# PCB-MIDDLE_FINAL.net
KiCad netlist of a schematic drawn in EAGLE
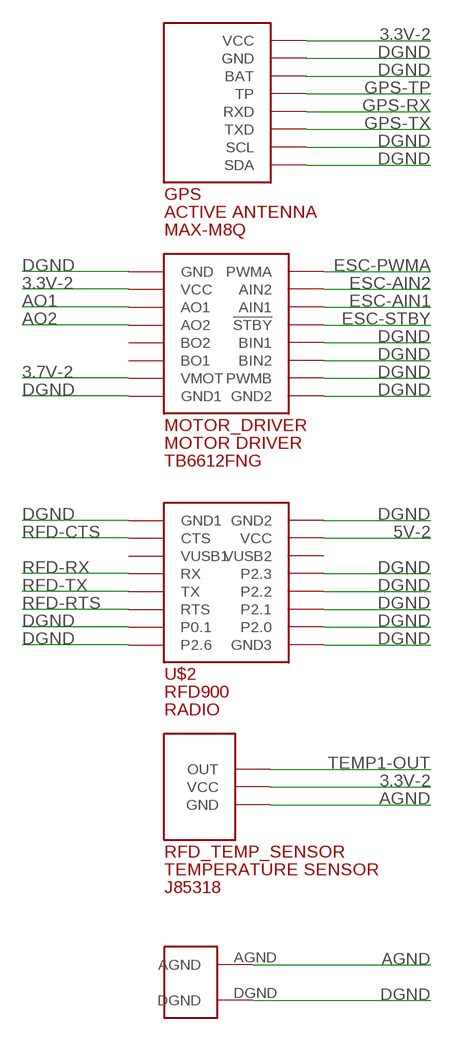
[diagram p0: schematic, sheet 1, part 1 of 2]
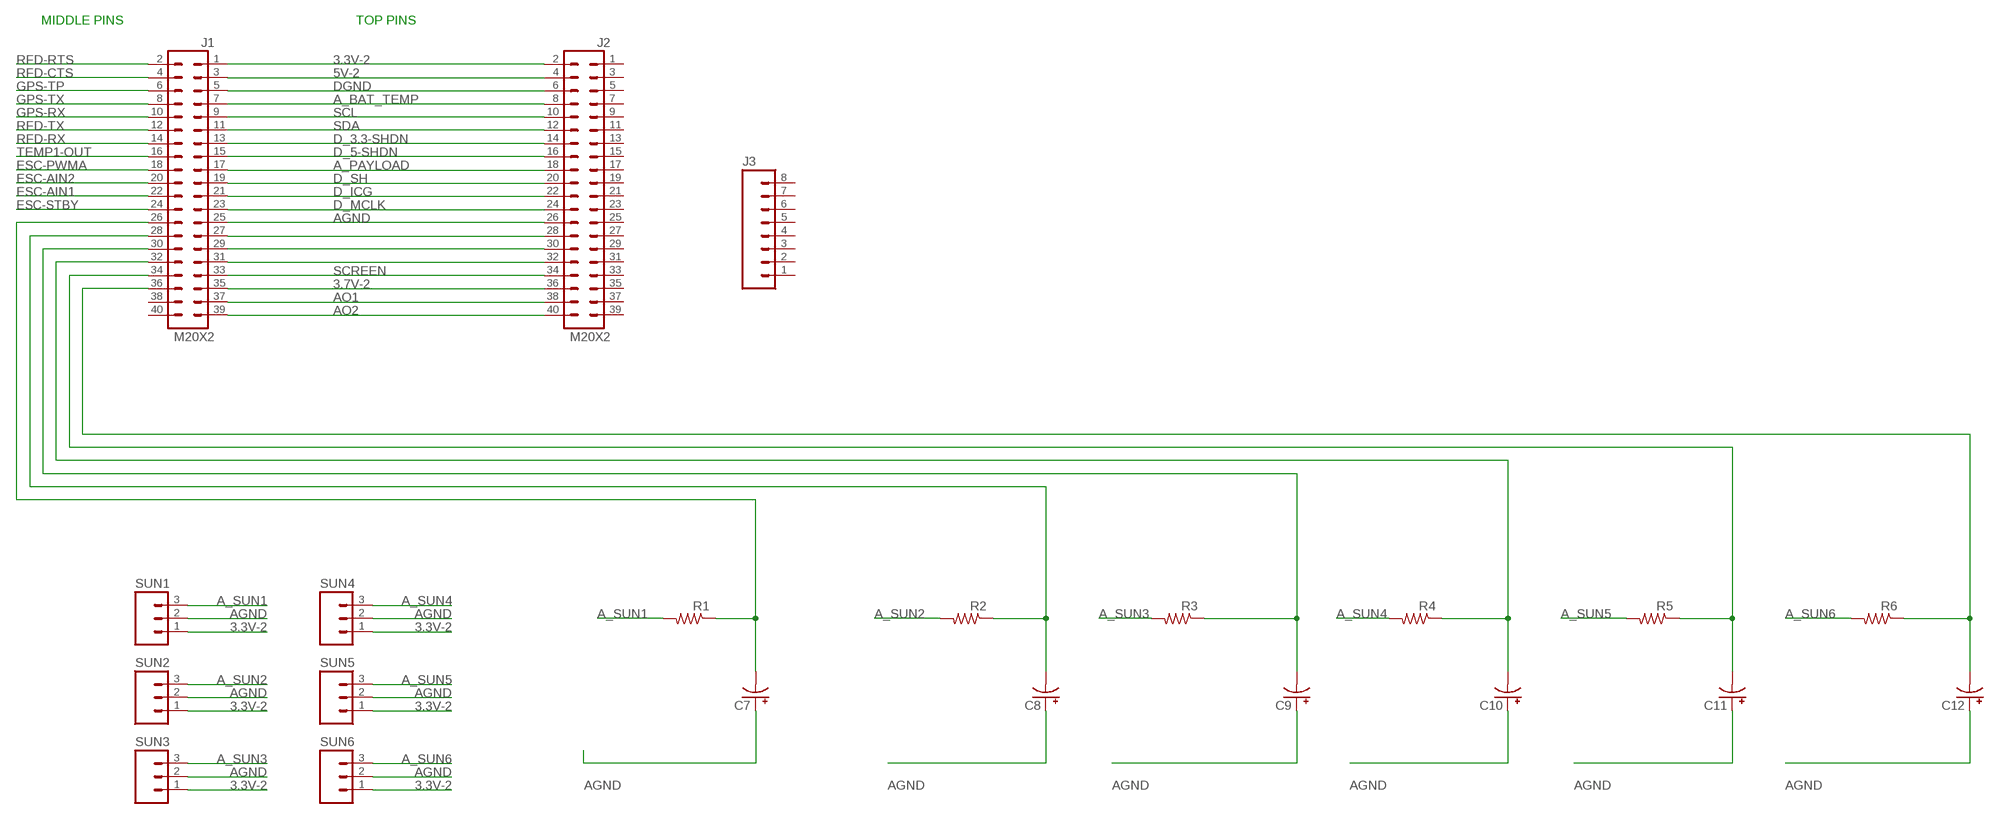
[diagram p1: schematic, sheet 1, part 2 of 2]

(export (version "E")
  (design (tool "Eeschema 10.0.6"))
  (components
    (comp (ref "C7")
      (value "100UF-25V-20%(PTH)")
      (footprint "eagle-import:CPOL-RADIAL-100UF-25V")
      (libsource (lib "eagle-import") (part "100UF-25V-20%(PTH)"))
    )
    (comp (ref "C8")
      (value "100UF-25V-20%(PTH)")
      (footprint "eagle-import:CPOL-RADIAL-100UF-25V")
      (libsource (lib "eagle-import") (part "100UF-25V-20%(PTH)"))
    )
    (comp (ref "C9")
      (value "100UF-25V-20%(PTH)")
      (footprint "eagle-import:CPOL-RADIAL-100UF-25V")
      (libsource (lib "eagle-import") (part "100UF-25V-20%(PTH)"))
    )
    (comp (ref "C10")
      (value "100UF-25V-20%(PTH)")
      (footprint "eagle-import:CPOL-RADIAL-100UF-25V")
      (libsource (lib "eagle-import") (part "100UF-25V-20%(PTH)"))
    )
    (comp (ref "C11")
      (value "100UF-25V-20%(PTH)")
      (footprint "eagle-import:CPOL-RADIAL-100UF-25V")
      (libsource (lib "eagle-import") (part "100UF-25V-20%(PTH)"))
    )
    (comp (ref "C12")
      (value "100UF-25V-20%(PTH)")
      (footprint "eagle-import:CPOL-RADIAL-100UF-25V")
      (libsource (lib "eagle-import") (part "100UF-25V-20%(PTH)"))
    )
    (comp (ref "GPS")
      (value "MAX-M8QDIP8")
      (footprint "eagle-import:DIP8")
      (libsource (lib "eagle-import") (part "MAX-M8QDIP8"))
    )
    (comp (ref "J1")
      (value "M20X2")
      (footprint "eagle-import:2X20")
      (libsource (lib "eagle-import") (part "M20X2"))
    )
    (comp (ref "J2")
      (value "M20X2")
      (footprint "eagle-import:2X20")
      (libsource (lib "eagle-import") (part "M20X2"))
    )
    (comp (ref "J3")
      (value "M08")
      (footprint "eagle-import:1X08_ROUND")
      (libsource (lib "eagle-import") (part "M08"))
    )
    (comp (ref "MOTOR_DRIVER")
      (value "MOTOR_DRIVER_DEV")
      (footprint "eagle-import:MOTOR_DRIVER")
      (libsource (lib "eagle-import") (part "MOTOR_DRIVER_DEV"))
    )
    (comp (ref "R1")
      (value "R-US_0204/5")
      (footprint "eagle-import:0204_5")
      (libsource (lib "eagle-import") (part "R-US_0204/5"))
    )
    (comp (ref "R2")
      (value "R-US_0204/5")
      (footprint "eagle-import:0204_5")
      (libsource (lib "eagle-import") (part "R-US_0204/5"))
    )
    (comp (ref "R3")
      (value "R-US_0204/5")
      (footprint "eagle-import:0204_5")
      (libsource (lib "eagle-import") (part "R-US_0204/5"))
    )
    (comp (ref "R4")
      (value "R-US_0204/5")
      (footprint "eagle-import:0204_5")
      (libsource (lib "eagle-import") (part "R-US_0204/5"))
    )
    (comp (ref "R5")
      (value "R-US_0204/5")
      (footprint "eagle-import:0204_5")
      (libsource (lib "eagle-import") (part "R-US_0204/5"))
    )
    (comp (ref "R6")
      (value "R-US_0204/5")
      (footprint "eagle-import:0204_5")
      (libsource (lib "eagle-import") (part "R-US_0204/5"))
    )
    (comp (ref "RFD_TEMP_SENSOR")
      (value "TEMP_SENSORDIP3")
      (footprint "eagle-import:DIP3")
      (libsource (lib "eagle-import") (part "TEMP_SENSORDIP3"))
    )
    (comp (ref "SUN1")
      (value "M03PTH")
      (footprint "eagle-import:1X03")
      (libsource (lib "eagle-import") (part "M03PTH"))
    )
    (comp (ref "SUN2")
      (value "M03PTH")
      (footprint "eagle-import:1X03")
      (libsource (lib "eagle-import") (part "M03PTH"))
    )
    (comp (ref "SUN3")
      (value "M03PTH")
      (footprint "eagle-import:1X03")
      (libsource (lib "eagle-import") (part "M03PTH"))
    )
    (comp (ref "SUN4")
      (value "M03PTH")
      (footprint "eagle-import:1X03")
      (libsource (lib "eagle-import") (part "M03PTH"))
    )
    (comp (ref "SUN5")
      (value "M03PTH")
      (footprint "eagle-import:1X03")
      (libsource (lib "eagle-import") (part "M03PTH"))
    )
    (comp (ref "SUN6")
      (value "M03PTH")
      (footprint "eagle-import:1X03")
      (libsource (lib "eagle-import") (part "M03PTH"))
    )
    (comp (ref "U$1")
      (value "GROUNDPLANECONNECTION_BOTTOM")
      (footprint "eagle-import:GROUNDPLANECONNECTION_BOTTOM")
      (libsource (lib "eagle-import") (part "GROUNDPLANECONNECTION_BOTTOM"))
    )
    (comp (ref "U$2")
      (value "RFD900")
      (footprint "eagle-import:RFD900_NEW")
      (libsource (lib "eagle-import") (part "RFD900"))
    )
  )
  (nets
    (net (code "1") (name "3.3V-2") (class "Default")
      (node (ref "GPS") (pin "VCC") (pinfunction "VCC_VCC") (pintype "bidirectional"))
      (node (ref "J1") (pin "1") (pinfunction "1_1") (pintype "passive"))
      (node (ref "J2") (pin "2") (pinfunction "2_2") (pintype "passive"))
      (node (ref "MOTOR_DRIVER") (pin "VCC") (pinfunction "VCC_VCC") (pintype "bidirectional"))
      (node (ref "RFD_TEMP_SENSOR") (pin "VCC") (pinfunction "VCC_VCC") (pintype "bidirectional"))
      (node (ref "SUN1") (pin "1") (pinfunction "1_1") (pintype "passive"))
      (node (ref "SUN2") (pin "1") (pinfunction "1_1") (pintype "passive"))
      (node (ref "SUN3") (pin "1") (pinfunction "1_1") (pintype "passive"))
      (node (ref "SUN4") (pin "1") (pinfunction "1_1") (pintype "passive"))
      (node (ref "SUN5") (pin "1") (pinfunction "1_1") (pintype "passive"))
      (node (ref "SUN6") (pin "1") (pinfunction "1_1") (pintype "passive"))
    )
    (net (code "2") (name "3.7V-2") (class "Default")
      (node (ref "J1") (pin "35") (pinfunction "35_35") (pintype "passive"))
      (node (ref "J2") (pin "36") (pinfunction "36_36") (pintype "passive"))
      (node (ref "MOTOR_DRIVER") (pin "VMOT") (pinfunction "VMOT_VMOT") (pintype "bidirectional"))
    )
    (net (code "3") (name "5V-2") (class "Default")
      (node (ref "J1") (pin "3") (pinfunction "3_3") (pintype "passive"))
      (node (ref "J2") (pin "4") (pinfunction "4_4") (pintype "passive"))
      (node (ref "U$2") (pin "VCC") (pinfunction "VCC_VCC") (pintype "bidirectional"))
    )
    (net (code "4") (name "AGND") (class "Default")
      (node (ref "C10") (pin "1") (pinfunction "+_1") (pintype "passive"))
      (node (ref "C11") (pin "1") (pinfunction "+_1") (pintype "passive"))
      (node (ref "C12") (pin "1") (pinfunction "+_1") (pintype "passive"))
      (node (ref "C7") (pin "1") (pinfunction "+_1") (pintype "passive"))
      (node (ref "C8") (pin "1") (pinfunction "+_1") (pintype "passive"))
      (node (ref "C9") (pin "1") (pinfunction "+_1") (pintype "passive"))
      (node (ref "J1") (pin "25") (pinfunction "25_25") (pintype "passive"))
      (node (ref "J2") (pin "26") (pinfunction "26_26") (pintype "passive"))
      (node (ref "RFD_TEMP_SENSOR") (pin "GND") (pinfunction "GND_GND") (pintype "bidirectional"))
      (node (ref "SUN1") (pin "2") (pinfunction "2_2") (pintype "passive"))
      (node (ref "SUN2") (pin "2") (pinfunction "2_2") (pintype "passive"))
      (node (ref "SUN3") (pin "2") (pinfunction "2_2") (pintype "passive"))
      (node (ref "SUN4") (pin "2") (pinfunction "2_2") (pintype "passive"))
      (node (ref "SUN5") (pin "2") (pinfunction "2_2") (pintype "passive"))
      (node (ref "SUN6") (pin "2") (pinfunction "2_2") (pintype "passive"))
      (node (ref "U$1") (pin "AGND") (pinfunction "AGND_AGND") (pintype "bidirectional"))
    )
    (net (code "5") (name "AO1") (class "Default")
      (node (ref "J1") (pin "37") (pinfunction "37_37") (pintype "passive"))
      (node (ref "J2") (pin "38") (pinfunction "38_38") (pintype "passive"))
      (node (ref "MOTOR_DRIVER") (pin "AO1") (pinfunction "AO1_AO1") (pintype "bidirectional"))
    )
    (net (code "6") (name "AO2") (class "Default")
      (node (ref "J1") (pin "39") (pinfunction "39_39") (pintype "passive"))
      (node (ref "J2") (pin "40") (pinfunction "40_40") (pintype "passive"))
      (node (ref "MOTOR_DRIVER") (pin "AO2") (pinfunction "AO2_AO2") (pintype "bidirectional"))
    )
    (net (code "7") (name "A_BAT_TEMP") (class "Default")
      (node (ref "J1") (pin "7") (pinfunction "7_7") (pintype "passive"))
      (node (ref "J2") (pin "8") (pinfunction "8_8") (pintype "passive"))
    )
    (net (code "8") (name "A_PAYLOAD") (class "Default")
      (node (ref "J1") (pin "17") (pinfunction "17_17") (pintype "passive"))
      (node (ref "J2") (pin "18") (pinfunction "18_18") (pintype "passive"))
    )
    (net (code "9") (name "A_SUN1") (class "Default")
      (node (ref "R1") (pin "2") (pinfunction "2_2") (pintype "passive"))
      (node (ref "SUN1") (pin "3") (pinfunction "3_3") (pintype "passive"))
    )
    (net (code "10") (name "A_SUN2") (class "Default")
      (node (ref "R2") (pin "2") (pinfunction "2_2") (pintype "passive"))
      (node (ref "SUN2") (pin "3") (pinfunction "3_3") (pintype "passive"))
    )
    (net (code "11") (name "A_SUN3") (class "Default")
      (node (ref "R3") (pin "2") (pinfunction "2_2") (pintype "passive"))
      (node (ref "SUN3") (pin "3") (pinfunction "3_3") (pintype "passive"))
    )
    (net (code "12") (name "A_SUN4") (class "Default")
      (node (ref "R4") (pin "2") (pinfunction "2_2") (pintype "passive"))
      (node (ref "SUN4") (pin "3") (pinfunction "3_3") (pintype "passive"))
    )
    (net (code "13") (name "A_SUN5") (class "Default")
      (node (ref "R5") (pin "2") (pinfunction "2_2") (pintype "passive"))
      (node (ref "SUN5") (pin "3") (pinfunction "3_3") (pintype "passive"))
    )
    (net (code "14") (name "A_SUN6") (class "Default")
      (node (ref "R6") (pin "2") (pinfunction "2_2") (pintype "passive"))
      (node (ref "SUN6") (pin "3") (pinfunction "3_3") (pintype "passive"))
    )
    (net (code "15") (name "DGND") (class "Default")
      (node (ref "GPS") (pin "BATT") (pinfunction "BAT_BATT") (pintype "bidirectional"))
      (node (ref "GPS") (pin "GND") (pinfunction "GND_GND") (pintype "bidirectional"))
      (node (ref "GPS") (pin "SCL") (pinfunction "SCL_SCL") (pintype "bidirectional"))
      (node (ref "GPS") (pin "SDA") (pinfunction "SDA_SDA") (pintype "bidirectional"))
      (node (ref "J1") (pin "5") (pinfunction "5_5") (pintype "passive"))
      (node (ref "J2") (pin "6") (pinfunction "6_6") (pintype "passive"))
      (node (ref "MOTOR_DRIVER") (pin "BIN1") (pinfunction "BIN1_BIN1") (pintype "bidirectional"))
      (node (ref "MOTOR_DRIVER") (pin "BIN2") (pinfunction "BIN2_BIN2") (pintype "bidirectional"))
      (node (ref "MOTOR_DRIVER") (pin "GND") (pinfunction "GND_GND") (pintype "bidirectional"))
      (node (ref "MOTOR_DRIVER") (pin "GND1") (pinfunction "GND1_GND1") (pintype "bidirectional"))
      (node (ref "MOTOR_DRIVER") (pin "GND2") (pinfunction "GND2_GND2") (pintype "bidirectional"))
      (node (ref "MOTOR_DRIVER") (pin "PWMB") (pinfunction "PWMB_PWMB") (pintype "bidirectional"))
      (node (ref "U$1") (pin "DGND") (pinfunction "DGND_DGND") (pintype "bidirectional"))
      (node (ref "U$2") (pin "GND1") (pinfunction "GND1_GND1") (pintype "bidirectional"))
      (node (ref "U$2") (pin "GND2") (pinfunction "GND2_GND2") (pintype "bidirectional"))
      (node (ref "U$2") (pin "GND3") (pinfunction "GND3_GND3") (pintype "bidirectional"))
      (node (ref "U$2") (pin "P0.1") (pinfunction "P0.1_P0.1") (pintype "bidirectional"))
      (node (ref "U$2") (pin "P2.0") (pinfunction "P2.0_P2.0") (pintype "bidirectional"))
      (node (ref "U$2") (pin "P2.1") (pinfunction "P2.1_P2.1") (pintype "bidirectional"))
      (node (ref "U$2") (pin "P2.2") (pinfunction "P2.2_P2.2") (pintype "bidirectional"))
      (node (ref "U$2") (pin "P2.3") (pinfunction "P2.3_P2.3") (pintype "bidirectional"))
      (node (ref "U$2") (pin "P2.6") (pinfunction "P2.6_P2.6") (pintype "bidirectional"))
    )
    (net (code "16") (name "D_3.3-SHDN") (class "Default")
      (node (ref "J1") (pin "13") (pinfunction "13_13") (pintype "passive"))
      (node (ref "J2") (pin "14") (pinfunction "14_14") (pintype "passive"))
    )
    (net (code "17") (name "D_5-SHDN") (class "Default")
      (node (ref "J1") (pin "15") (pinfunction "15_15") (pintype "passive"))
      (node (ref "J2") (pin "16") (pinfunction "16_16") (pintype "passive"))
    )
    (net (code "18") (name "D_ICG") (class "Default")
      (node (ref "J1") (pin "21") (pinfunction "21_21") (pintype "passive"))
      (node (ref "J2") (pin "22") (pinfunction "22_22") (pintype "passive"))
    )
    (net (code "19") (name "D_MCLK") (class "Default")
      (node (ref "J1") (pin "23") (pinfunction "23_23") (pintype "passive"))
      (node (ref "J2") (pin "24") (pinfunction "24_24") (pintype "passive"))
    )
    (net (code "20") (name "D_SH") (class "Default")
      (node (ref "J1") (pin "19") (pinfunction "19_19") (pintype "passive"))
      (node (ref "J2") (pin "20") (pinfunction "20_20") (pintype "passive"))
    )
    (net (code "21") (name "ESC-AIN1") (class "Default")
      (node (ref "J1") (pin "22") (pinfunction "22_22") (pintype "passive"))
      (node (ref "MOTOR_DRIVER") (pin "AIN1") (pinfunction "AIN1_AIN1") (pintype "bidirectional"))
    )
    (net (code "22") (name "ESC-AIN2") (class "Default")
      (node (ref "J1") (pin "20") (pinfunction "20_20") (pintype "passive"))
      (node (ref "MOTOR_DRIVER") (pin "AIN2") (pinfunction "AIN2_AIN2") (pintype "bidirectional"))
    )
    (net (code "23") (name "ESC-PWMA") (class "Default")
      (node (ref "J1") (pin "18") (pinfunction "18_18") (pintype "passive"))
      (node (ref "MOTOR_DRIVER") (pin "PWMA") (pinfunction "PWMA_PWMA") (pintype "bidirectional"))
    )
    (net (code "24") (name "ESC-STBY") (class "Default")
      (node (ref "J1") (pin "24") (pinfunction "24_24") (pintype "passive"))
      (node (ref "MOTOR_DRIVER") (pin "!STBY") (pinfunction "~{STBY}_!STBY") (pintype "bidirectional"))
    )
    (net (code "25") (name "GPS-RX") (class "Default")
      (node (ref "GPS") (pin "RXD") (pinfunction "RXD_RXD") (pintype "bidirectional"))
      (node (ref "J1") (pin "10") (pinfunction "10_10") (pintype "passive"))
    )
    (net (code "26") (name "GPS-TP") (class "Default")
      (node (ref "GPS") (pin "TP") (pinfunction "TP_TP") (pintype "bidirectional"))
      (node (ref "J1") (pin "6") (pinfunction "6_6") (pintype "passive"))
    )
    (net (code "27") (name "GPS-TX") (class "Default")
      (node (ref "GPS") (pin "TXD") (pinfunction "TXD_TXD") (pintype "bidirectional"))
      (node (ref "J1") (pin "8") (pinfunction "8_8") (pintype "passive"))
    )
    (net (code "28") (name "Net-(C7--)") (class "Default")
      (node (ref "C7") (pin "2") (pinfunction "-_2") (pintype "passive"))
      (node (ref "J1") (pin "26") (pinfunction "26_26") (pintype "passive"))
      (node (ref "R1") (pin "1") (pinfunction "1_1") (pintype "passive"))
    )
    (net (code "29") (name "Net-(C8--)") (class "Default")
      (node (ref "C8") (pin "2") (pinfunction "-_2") (pintype "passive"))
      (node (ref "J1") (pin "28") (pinfunction "28_28") (pintype "passive"))
      (node (ref "R2") (pin "1") (pinfunction "1_1") (pintype "passive"))
    )
    (net (code "30") (name "Net-(C9--)") (class "Default")
      (node (ref "C9") (pin "2") (pinfunction "-_2") (pintype "passive"))
      (node (ref "J1") (pin "30") (pinfunction "30_30") (pintype "passive"))
      (node (ref "R3") (pin "1") (pinfunction "1_1") (pintype "passive"))
    )
    (net (code "31") (name "Net-(C10--)") (class "Default")
      (node (ref "C10") (pin "2") (pinfunction "-_2") (pintype "passive"))
      (node (ref "J1") (pin "32") (pinfunction "32_32") (pintype "passive"))
      (node (ref "R4") (pin "1") (pinfunction "1_1") (pintype "passive"))
    )
    (net (code "32") (name "Net-(C11--)") (class "Default")
      (node (ref "C11") (pin "2") (pinfunction "-_2") (pintype "passive"))
      (node (ref "J1") (pin "34") (pinfunction "34_34") (pintype "passive"))
      (node (ref "R5") (pin "1") (pinfunction "1_1") (pintype "passive"))
    )
    (net (code "33") (name "Net-(C12--)") (class "Default")
      (node (ref "C12") (pin "2") (pinfunction "-_2") (pintype "passive"))
      (node (ref "J1") (pin "36") (pinfunction "36_36") (pintype "passive"))
      (node (ref "R6") (pin "1") (pinfunction "1_1") (pintype "passive"))
    )
    (net (code "34") (name "Net-(J1-Pad27)") (class "Default")
      (node (ref "J1") (pin "27") (pinfunction "27_27") (pintype "passive"))
      (node (ref "J2") (pin "28") (pinfunction "28_28") (pintype "passive"))
    )
    (net (code "35") (name "Net-(J1-Pad29)") (class "Default")
      (node (ref "J1") (pin "29") (pinfunction "29_29") (pintype "passive"))
      (node (ref "J2") (pin "30") (pinfunction "30_30") (pintype "passive"))
    )
    (net (code "36") (name "Net-(J1-Pad31)") (class "Default")
      (node (ref "J1") (pin "31") (pinfunction "31_31") (pintype "passive"))
      (node (ref "J2") (pin "32") (pinfunction "32_32") (pintype "passive"))
    )
    (net (code "37") (name "RFD-CTS") (class "Default")
      (node (ref "J1") (pin "4") (pinfunction "4_4") (pintype "passive"))
      (node (ref "U$2") (pin "CTS") (pinfunction "CTS_CTS") (pintype "bidirectional"))
    )
    (net (code "38") (name "RFD-RTS") (class "Default")
      (node (ref "J1") (pin "2") (pinfunction "2_2") (pintype "passive"))
      (node (ref "U$2") (pin "RTS") (pinfunction "RTS_RTS") (pintype "bidirectional"))
    )
    (net (code "39") (name "RFD-RX") (class "Default")
      (node (ref "J1") (pin "14") (pinfunction "14_14") (pintype "passive"))
      (node (ref "U$2") (pin "RX") (pinfunction "RX_RX") (pintype "bidirectional"))
    )
    (net (code "40") (name "RFD-TX") (class "Default")
      (node (ref "J1") (pin "12") (pinfunction "12_12") (pintype "passive"))
      (node (ref "U$2") (pin "TX") (pinfunction "TX_TX") (pintype "bidirectional"))
    )
    (net (code "41") (name "SCL") (class "Default")
      (node (ref "J1") (pin "9") (pinfunction "9_9") (pintype "passive"))
      (node (ref "J2") (pin "10") (pinfunction "10_10") (pintype "passive"))
    )
    (net (code "42") (name "SCREEN") (class "Default")
      (node (ref "J1") (pin "33") (pinfunction "33_33") (pintype "passive"))
      (node (ref "J2") (pin "34") (pinfunction "34_34") (pintype "passive"))
    )
    (net (code "43") (name "SDA") (class "Default")
      (node (ref "J1") (pin "11") (pinfunction "11_11") (pintype "passive"))
      (node (ref "J2") (pin "12") (pinfunction "12_12") (pintype "passive"))
    )
    (net (code "44") (name "TEMP1-OUT") (class "Default")
      (node (ref "J1") (pin "16") (pinfunction "16_16") (pintype "passive"))
      (node (ref "RFD_TEMP_SENSOR") (pin "OUT") (pinfunction "OUT_OUT") (pintype "bidirectional"))
    )
    (net (code "45") (name "unconnected-(J1-Pad38)") (class "Default")
      (node (ref "J1") (pin "38") (pinfunction "38_38") (pintype "passive"))
    )
    (net (code "46") (name "unconnected-(J1-Pad40)") (class "Default")
      (node (ref "J1") (pin "40") (pinfunction "40_40") (pintype "passive"))
    )
    (net (code "47") (name "unconnected-(J2-Pad1)") (class "Default")
      (node (ref "J2") (pin "1") (pinfunction "1_1") (pintype "passive"))
    )
    (net (code "48") (name "unconnected-(J2-Pad3)") (class "Default")
      (node (ref "J2") (pin "3") (pinfunction "3_3") (pintype "passive"))
    )
    (net (code "49") (name "unconnected-(J2-Pad5)") (class "Default")
      (node (ref "J2") (pin "5") (pinfunction "5_5") (pintype "passive"))
    )
    (net (code "50") (name "unconnected-(J2-Pad7)") (class "Default")
      (node (ref "J2") (pin "7") (pinfunction "7_7") (pintype "passive"))
    )
    (net (code "51") (name "unconnected-(J2-Pad9)") (class "Default")
      (node (ref "J2") (pin "9") (pinfunction "9_9") (pintype "passive"))
    )
    (net (code "52") (name "unconnected-(J2-Pad11)") (class "Default")
      (node (ref "J2") (pin "11") (pinfunction "11_11") (pintype "passive"))
    )
    (net (code "53") (name "unconnected-(J2-Pad13)") (class "Default")
      (node (ref "J2") (pin "13") (pinfunction "13_13") (pintype "passive"))
    )
    (net (code "54") (name "unconnected-(J2-Pad15)") (class "Default")
      (node (ref "J2") (pin "15") (pinfunction "15_15") (pintype "passive"))
    )
    (net (code "55") (name "unconnected-(J2-Pad17)") (class "Default")
      (node (ref "J2") (pin "17") (pinfunction "17_17") (pintype "passive"))
    )
    (net (code "56") (name "unconnected-(J2-Pad19)") (class "Default")
      (node (ref "J2") (pin "19") (pinfunction "19_19") (pintype "passive"))
    )
    (net (code "57") (name "unconnected-(J2-Pad21)") (class "Default")
      (node (ref "J2") (pin "21") (pinfunction "21_21") (pintype "passive"))
    )
    (net (code "58") (name "unconnected-(J2-Pad23)") (class "Default")
      (node (ref "J2") (pin "23") (pinfunction "23_23") (pintype "passive"))
    )
    (net (code "59") (name "unconnected-(J2-Pad25)") (class "Default")
      (node (ref "J2") (pin "25") (pinfunction "25_25") (pintype "passive"))
    )
    (net (code "60") (name "unconnected-(J2-Pad27)") (class "Default")
      (node (ref "J2") (pin "27") (pinfunction "27_27") (pintype "passive"))
    )
    (net (code "61") (name "unconnected-(J2-Pad29)") (class "Default")
      (node (ref "J2") (pin "29") (pinfunction "29_29") (pintype "passive"))
    )
    (net (code "62") (name "unconnected-(J2-Pad31)") (class "Default")
      (node (ref "J2") (pin "31") (pinfunction "31_31") (pintype "passive"))
    )
    (net (code "63") (name "unconnected-(J2-Pad33)") (class "Default")
      (node (ref "J2") (pin "33") (pinfunction "33_33") (pintype "passive"))
    )
    (net (code "64") (name "unconnected-(J2-Pad35)") (class "Default")
      (node (ref "J2") (pin "35") (pinfunction "35_35") (pintype "passive"))
    )
    (net (code "65") (name "unconnected-(J2-Pad37)") (class "Default")
      (node (ref "J2") (pin "37") (pinfunction "37_37") (pintype "passive"))
    )
    (net (code "66") (name "unconnected-(J2-Pad39)") (class "Default")
      (node (ref "J2") (pin "39") (pinfunction "39_39") (pintype "passive"))
    )
    (net (code "67") (name "unconnected-(J3-Pad1)") (class "Default")
      (node (ref "J3") (pin "1") (pinfunction "1_1") (pintype "passive"))
    )
    (net (code "68") (name "unconnected-(J3-Pad2)") (class "Default")
      (node (ref "J3") (pin "2") (pinfunction "2_2") (pintype "passive"))
    )
    (net (code "69") (name "unconnected-(J3-Pad3)") (class "Default")
      (node (ref "J3") (pin "3") (pinfunction "3_3") (pintype "passive"))
    )
    (net (code "70") (name "unconnected-(J3-Pad4)") (class "Default")
      (node (ref "J3") (pin "4") (pinfunction "4_4") (pintype "passive"))
    )
    (net (code "71") (name "unconnected-(J3-Pad5)") (class "Default")
      (node (ref "J3") (pin "5") (pinfunction "5_5") (pintype "passive"))
    )
    (net (code "72") (name "unconnected-(J3-Pad6)") (class "Default")
      (node (ref "J3") (pin "6") (pinfunction "6_6") (pintype "passive"))
    )
    (net (code "73") (name "unconnected-(J3-Pad7)") (class "Default")
      (node (ref "J3") (pin "7") (pinfunction "7_7") (pintype "passive"))
    )
    (net (code "74") (name "unconnected-(J3-Pad8)") (class "Default")
      (node (ref "J3") (pin "8") (pinfunction "8_8") (pintype "passive"))
    )
    (net (code "75") (name "unconnected-(MOTOR_DRIVER-PadBO1)") (class "Default")
      (node (ref "MOTOR_DRIVER") (pin "BO1") (pinfunction "BO1_BO1") (pintype "bidirectional"))
    )
    (net (code "76") (name "unconnected-(MOTOR_DRIVER-PadBO2)") (class "Default")
      (node (ref "MOTOR_DRIVER") (pin "BO2") (pinfunction "BO2_BO2") (pintype "bidirectional"))
    )
    (net (code "77") (name "unconnected-(U$2-PadVUSB1)") (class "Default")
      (node (ref "U$2") (pin "VUSB1") (pinfunction "VUSB1_VUSB1") (pintype "bidirectional"))
    )
    (net (code "78") (name "unconnected-(U$2-PadVUSB2)") (class "Default")
      (node (ref "U$2") (pin "VUSB2") (pinfunction "VUSB2_VUSB2") (pintype "bidirectional"))
    )
  )
)
